# 05_Buzzer.net
KiCad netlist of a schematic drawn in Altium Designer
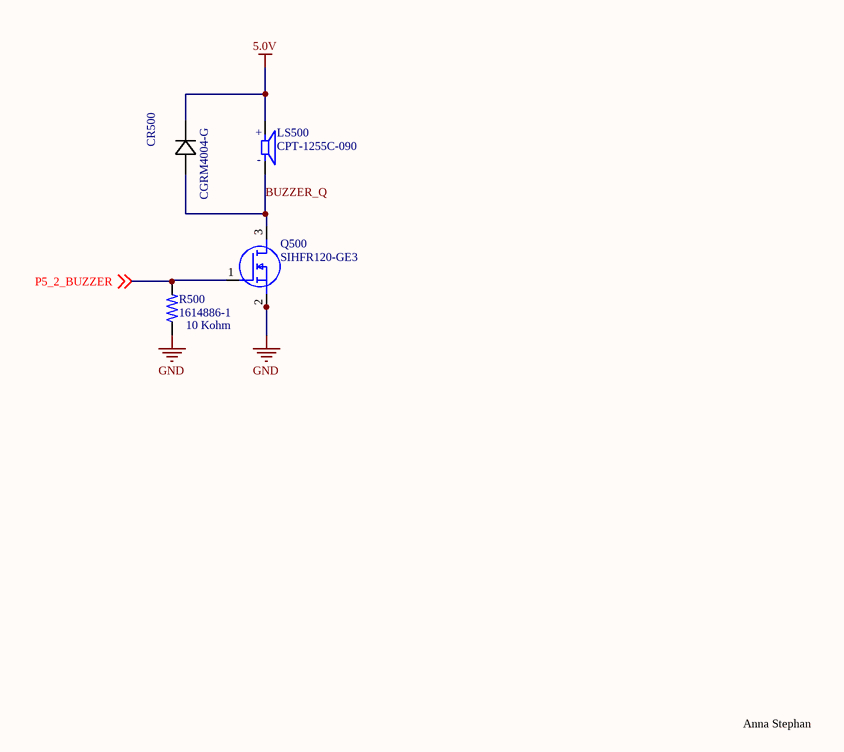
[diagram p0: 05_Buzzer.SchDoc]

(export (version "E")
  (design (tool "Eeschema 10.0.6"))
  (components
    (comp (ref "CR500")
      (value "CGRM4004-G")
      (footprint "CGRM")
      (description "No Description Available")
      (fields (field (name "COPYRIGHT") "Copyright (C) 2022 Ultra Librarian. All rights reserved."))
      (libsource (lib "453lib") (part "CGRM4004-G"))
    )
    (comp (ref "LS500")
      (value "CPT-1255C-090")
      (footprint "CUI_CPT-1255C-090")
      (description "12 mm, 20 Vp-p, 80 dB, Through Hole, Piezo Audio Transducer Buzzer")
      (fields (field (name "MF") "CUI Devices") (field (name "DIGIKEY PART NO.") "102-3752-ND"))
      (libsource (lib "453lib") (part "CPT-1255C-090"))
    )
    (comp (ref "Q500")
      (value "SIHFR120-GE3")
      (footprint "SIHFR120GE3")
      (description "MOSFET (N-Channel)")
      (fields (field (name "MOUSER2 PART NUMBER") "78-SIHFR120-GE3"))
      (libsource (lib "453lib") (part "SIHFR120-GE3"))
    )
    (comp (ref "R500")
      (value "1614886-1")
      (footprint "RESC2012X65N:RESC2012X65N")
      (description "CPF0805 10K 0.1% 25PPM 5K RL")
      (fields (field (name "TOLERANCE") ".1%") (field (name "MF") "TE Connectivity"))
      (libsource (lib "453lib") (part "1614886-1"))
    )
  )
  (nets
    (net (code "1") (name "/BUZZER_Q") (class "Default")
      (node (ref "CR500") (pin "2") (pinfunction "12_2") (pintype "passive"))
      (node (ref "LS500") (pin "N") (pinfunction "N_N") (pintype "passive"))
      (node (ref "Q500") (pin "3") (pinfunction "D_3") (pintype "passive"))
    )
    (net (code "2") (name "5.0V") (class "Default")
      (node (ref "CR500") (pin "1") (pinfunction "11_1") (pintype "passive"))
      (node (ref "LS500") (pin "P") (pinfunction "P_P") (pintype "passive"))
    )
    (net (code "3") (name "GND") (class "Default")
      (node (ref "Q500") (pin "2") (pinfunction "S_2") (pintype "passive"))
      (node (ref "R500") (pin "1") (pinfunction "1_1") (pintype "passive"))
    )
    (net (code "4") (name "P5_2_BUZZER") (class "Default")
      (node (ref "Q500") (pin "1") (pinfunction "G_1") (pintype "passive"))
      (node (ref "R500") (pin "2") (pinfunction "2_2") (pintype "passive"))
    )
  )
)
